# upperArm.net
KiCad netlist of a schematic drawn in EAGLE
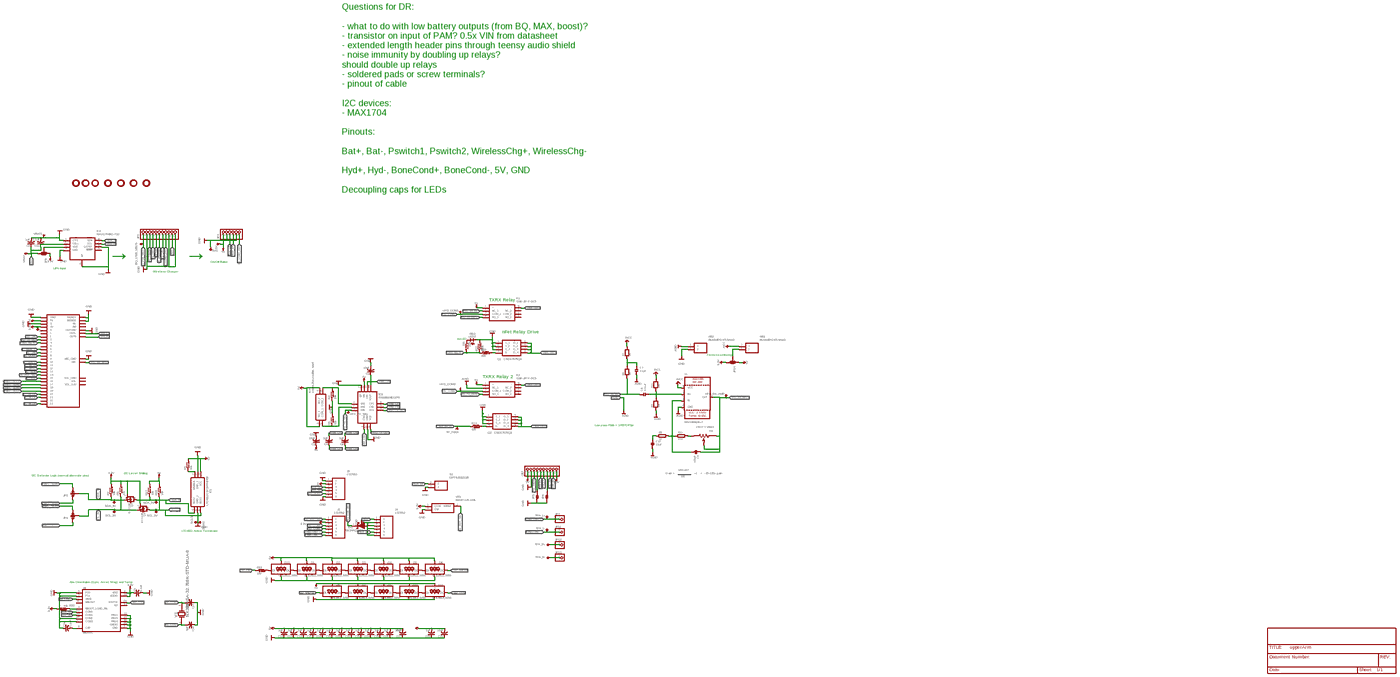
[diagram p0: schematic, sheet 1, overview]
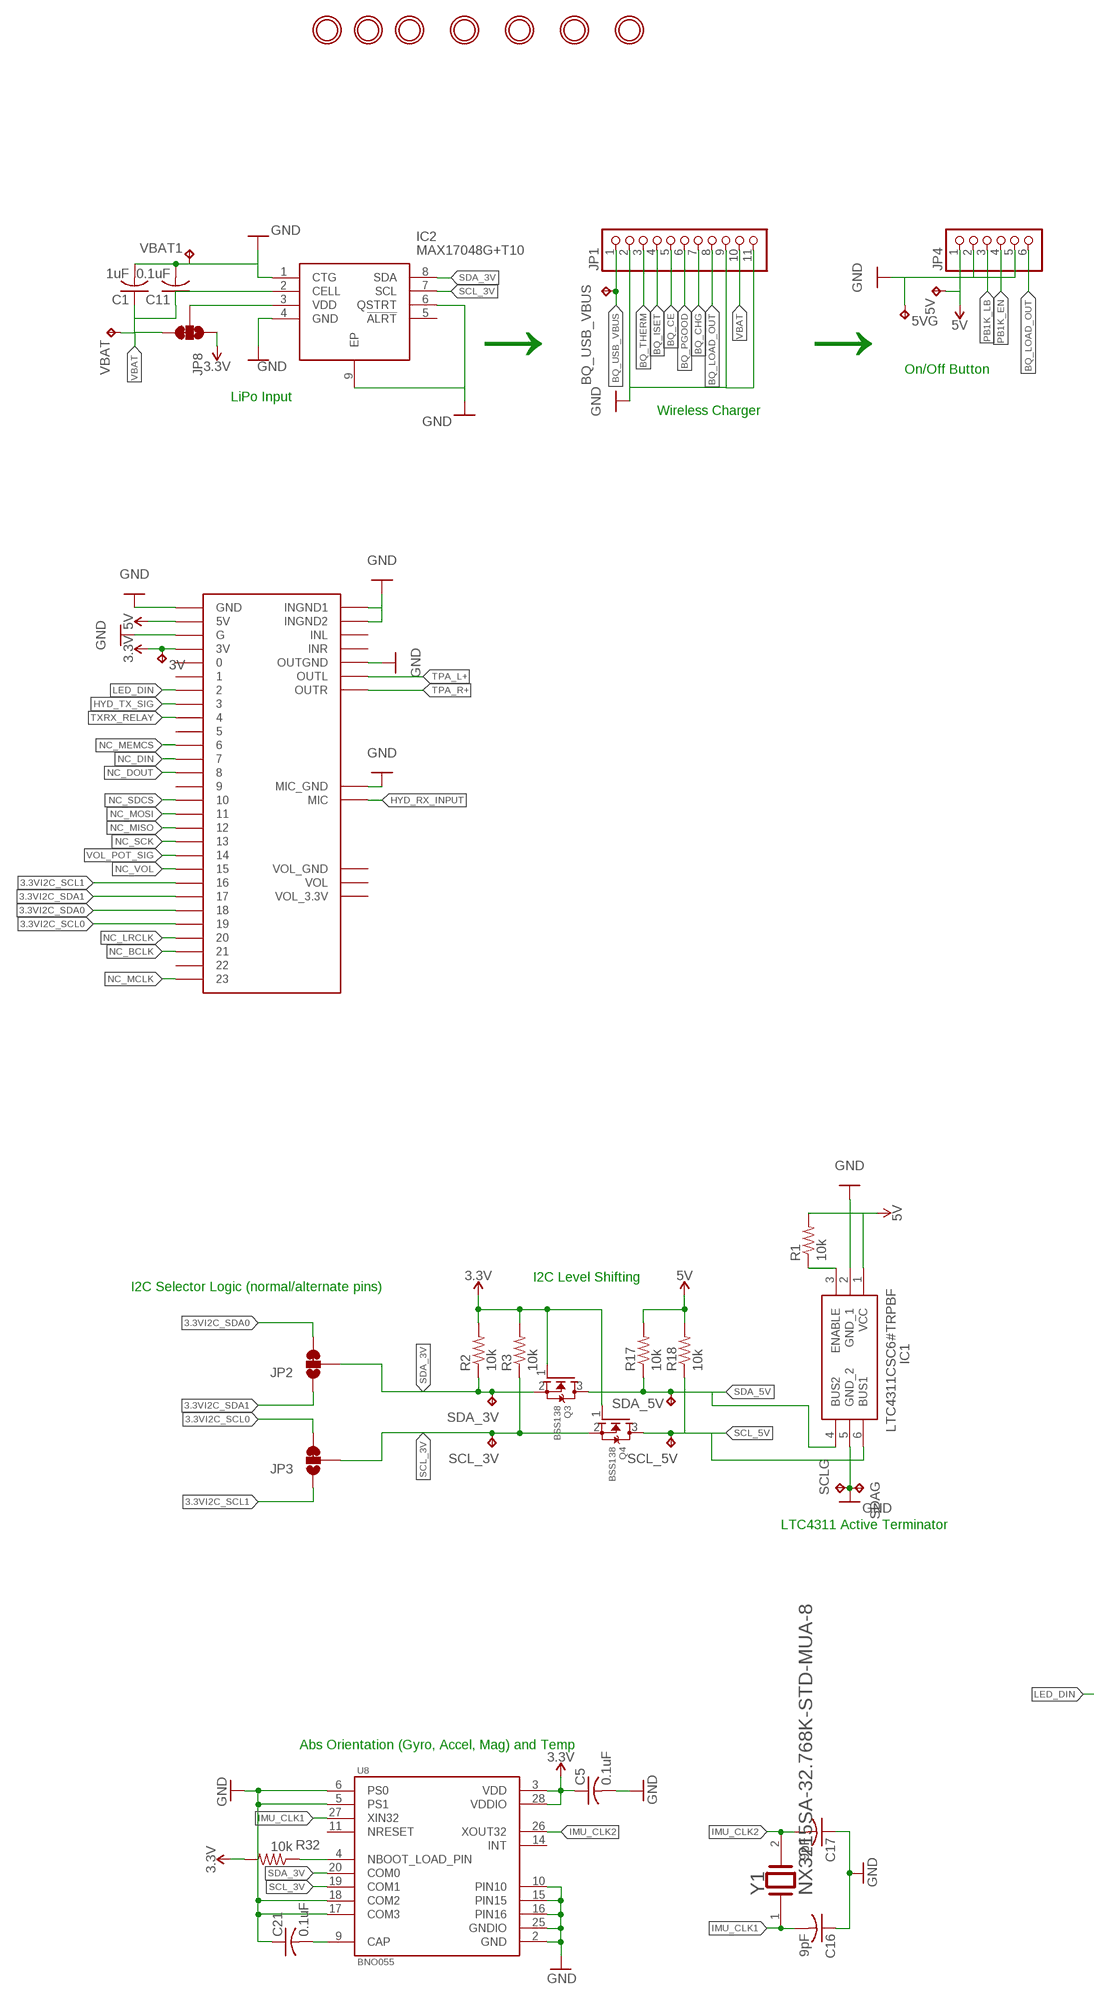
[diagram p1: schematic, sheet 1, part 1 of 4]
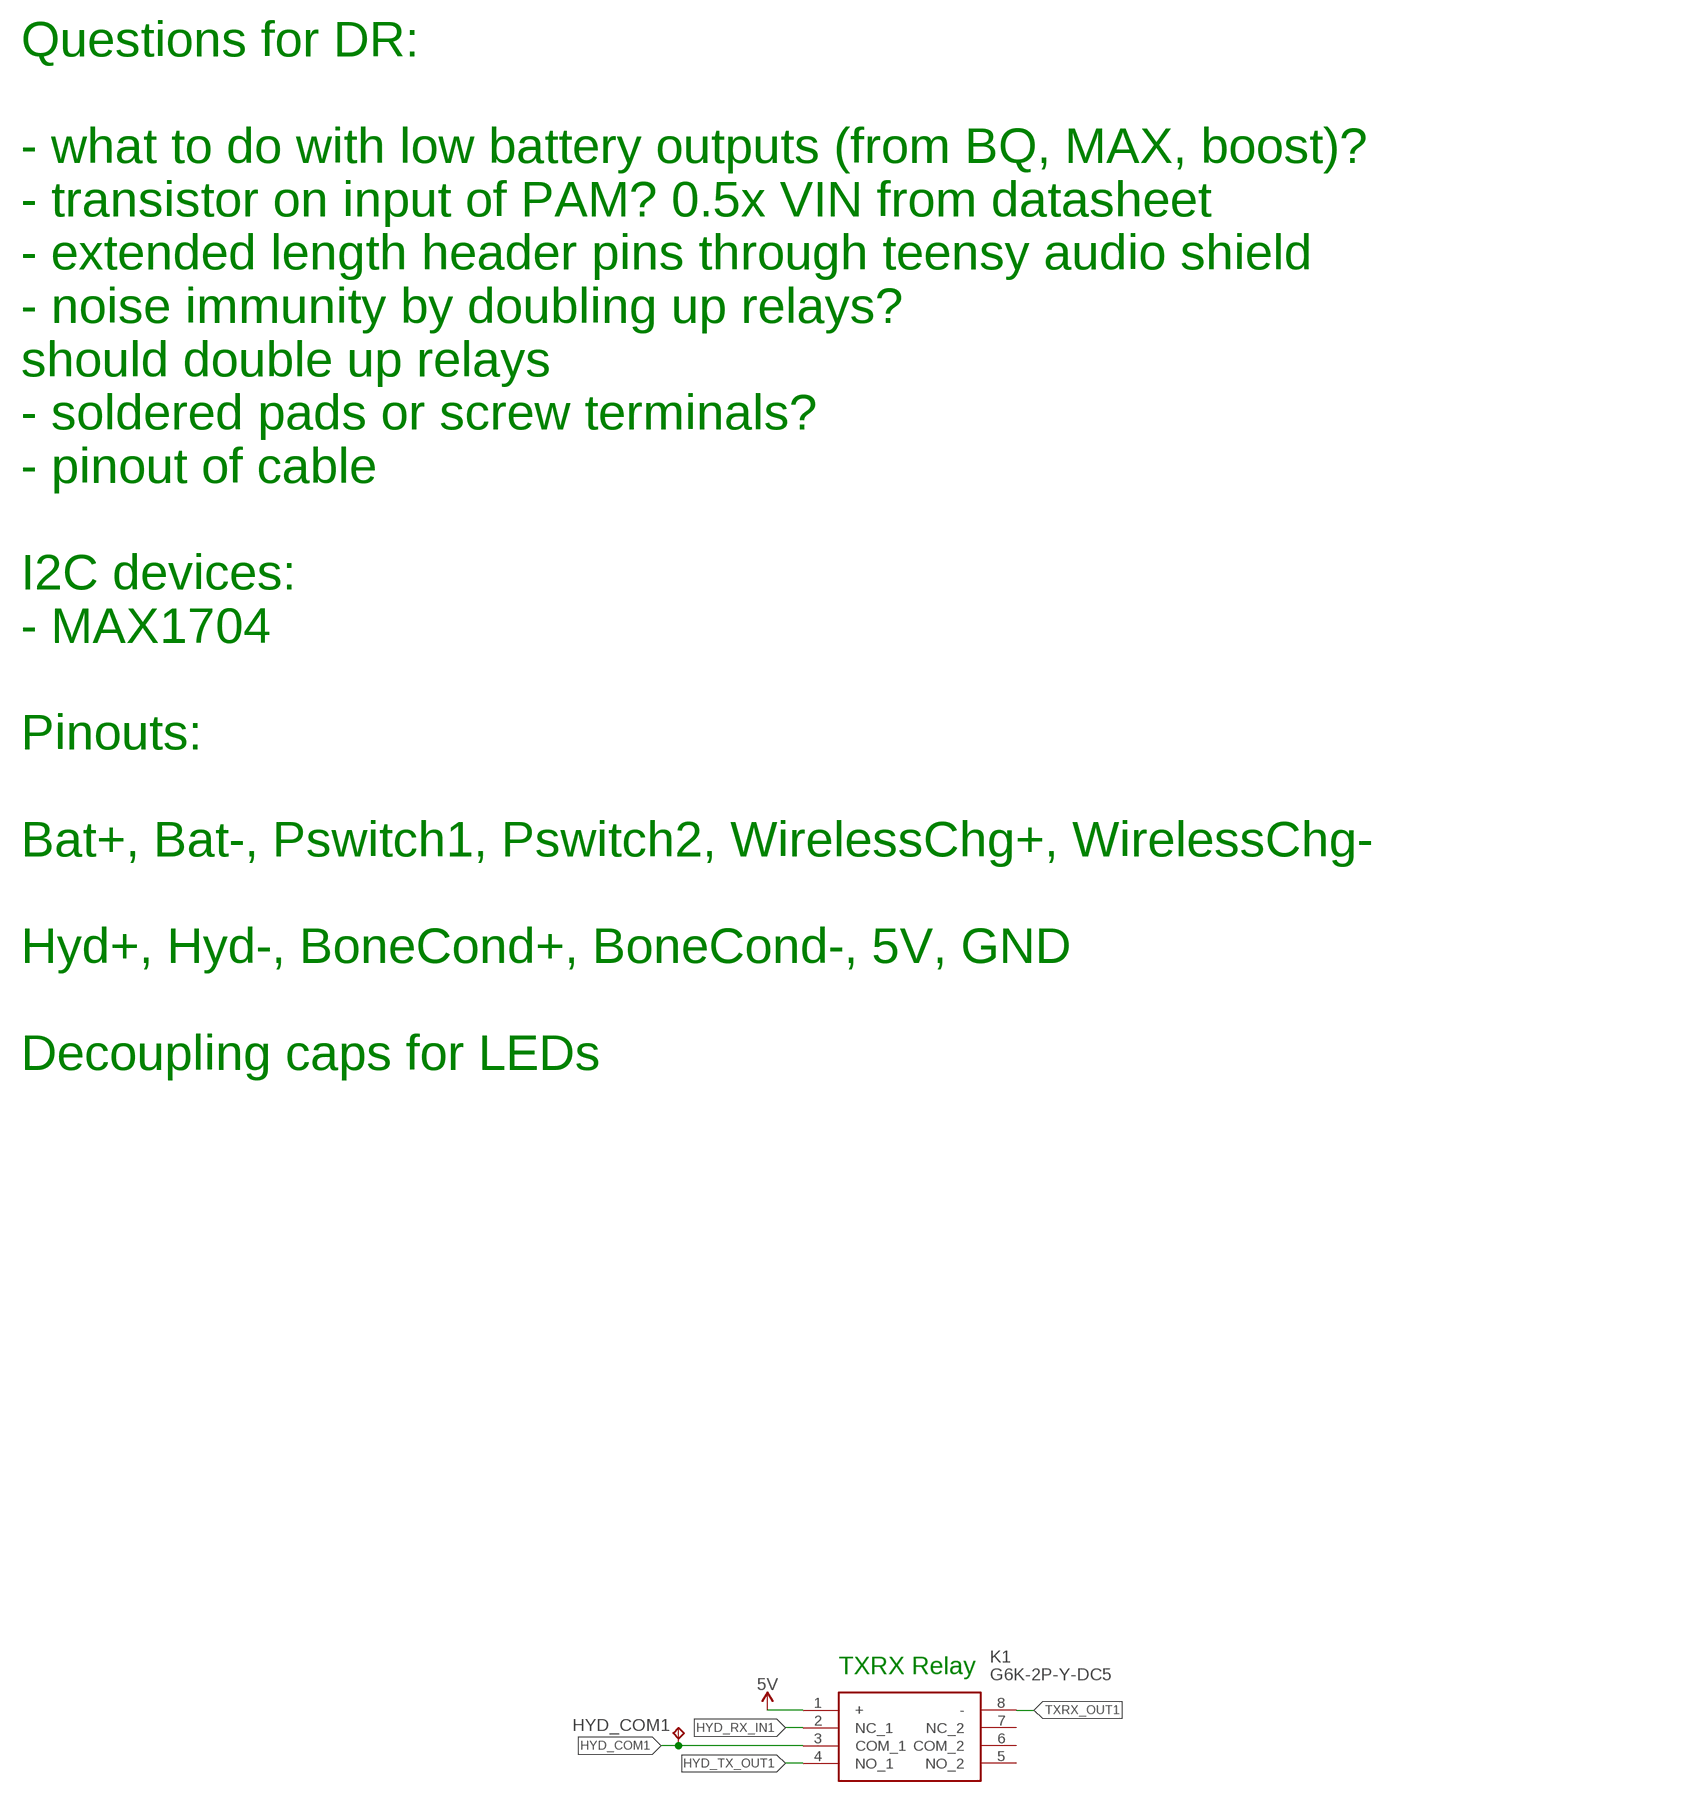
[diagram p2: schematic, sheet 1, part 2 of 4]
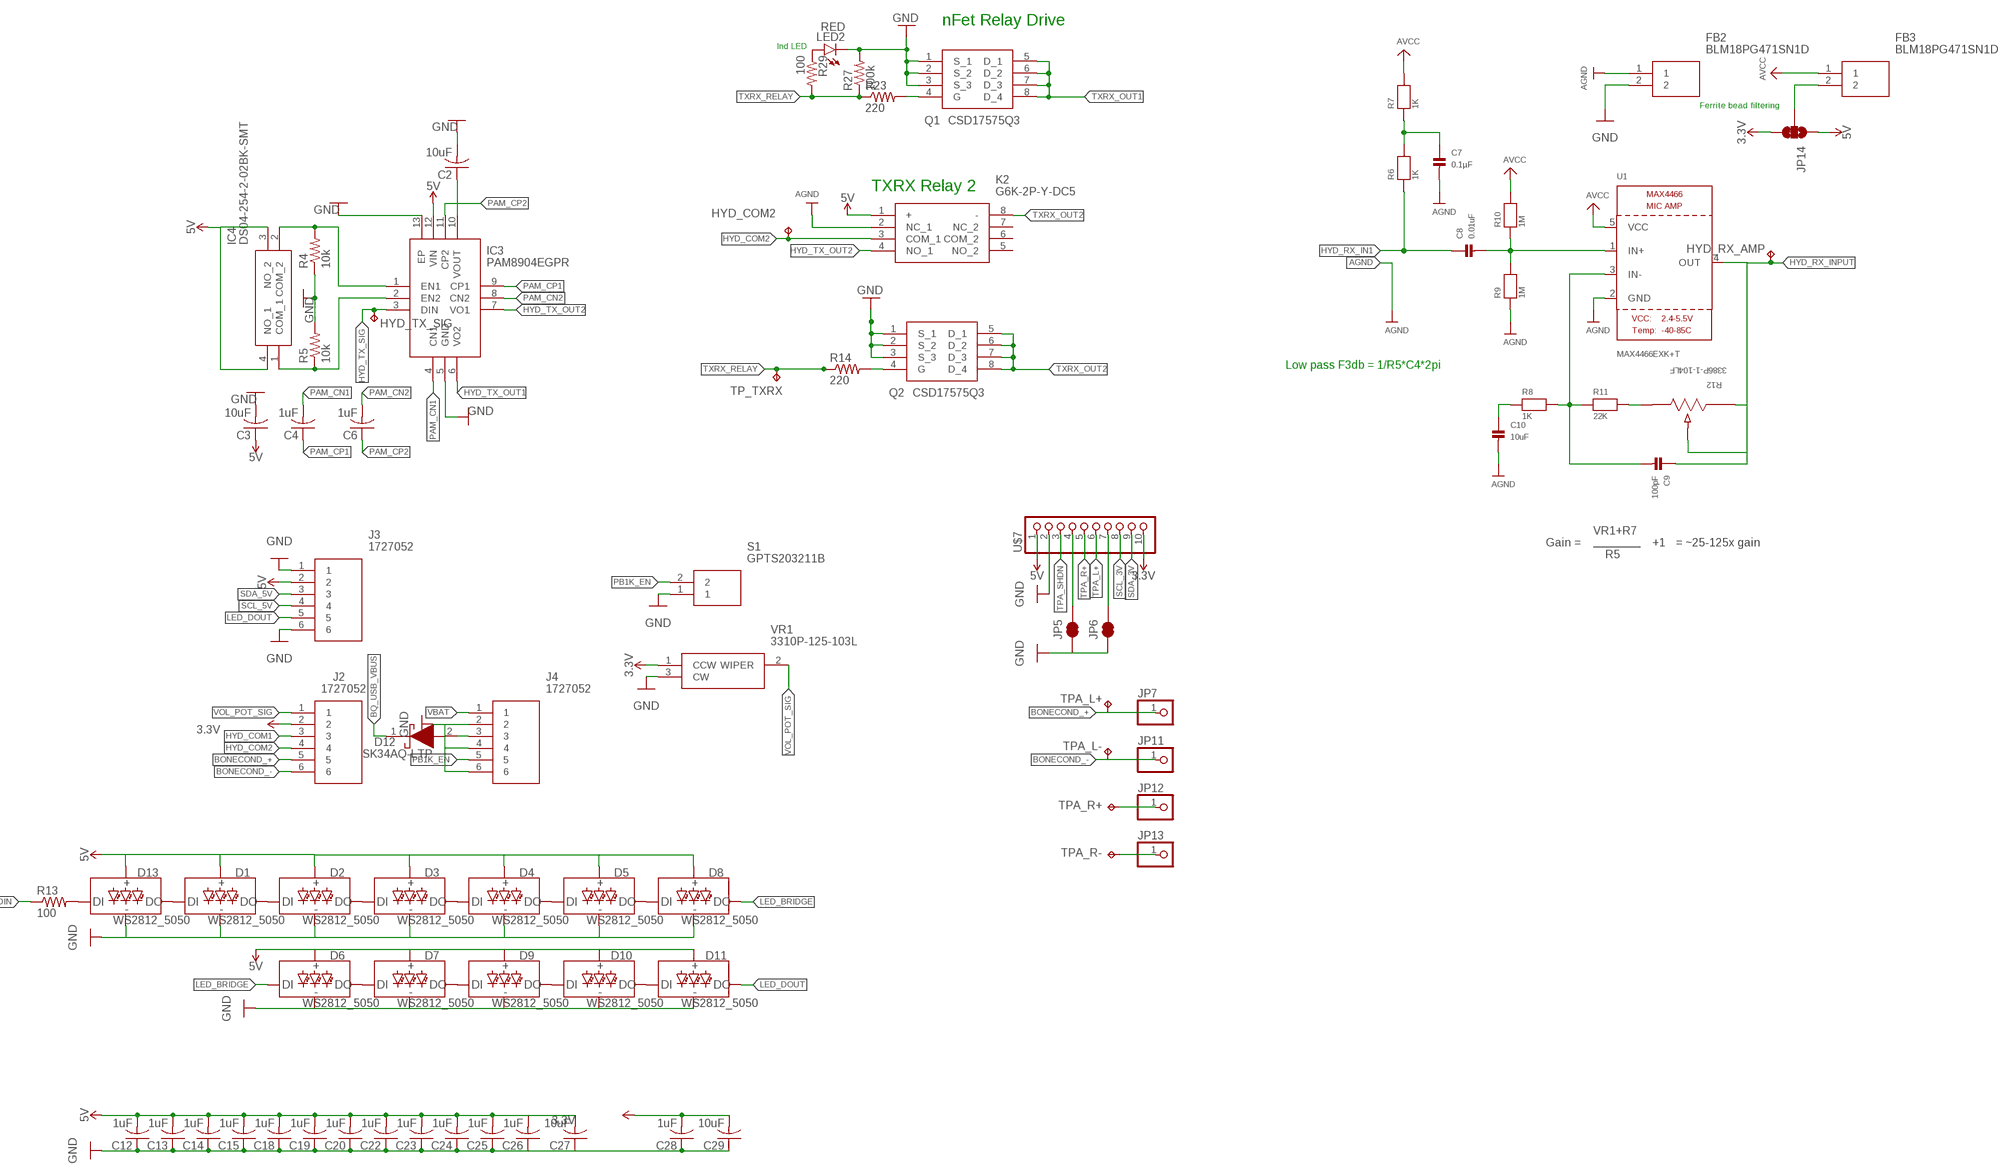
[diagram p3: schematic, sheet 1, part 3 of 4]
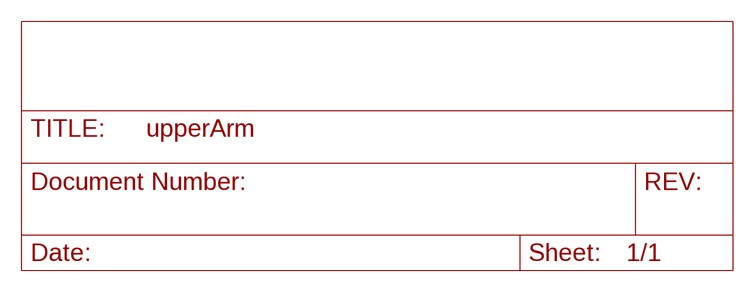
[diagram p4: schematic, sheet 1, part 4 of 4]

(export (version "E")
  (design (tool "Eeschema 10.0.6"))
  (components
    (comp (ref "3V")
      (value "TPB1,27")
      (footprint "eagle-import:B1,27")
      (libsource (lib "eagle-import") (part "TPB1,27"))
    )
    (comp (ref "5V")
      (value "TPB1,27")
      (footprint "eagle-import:B1,27")
      (libsource (lib "eagle-import") (part "TPB1,27"))
    )
    (comp (ref "5VG")
      (value "TPB1,27")
      (footprint "eagle-import:B1,27")
      (libsource (lib "eagle-import") (part "TPB1,27"))
    )
    (comp (ref "BQ_USB_VBUS")
      (value "TPB1,27")
      (footprint "eagle-import:B1,27")
      (libsource (lib "eagle-import") (part "TPB1,27"))
    )
    (comp (ref "C1")
      (value "1uF")
      (footprint "eagle-import:C0805")
      (libsource (lib "eagle-import") (part "C-USC0805"))
    )
    (comp (ref "C2")
      (value "10uF")
      (footprint "eagle-import:C0805")
      (libsource (lib "eagle-import") (part "C-USC0805"))
    )
    (comp (ref "C3")
      (value "10uF")
      (footprint "eagle-import:C0805")
      (libsource (lib "eagle-import") (part "C-USC0805"))
    )
    (comp (ref "C4")
      (value "1uF")
      (footprint "eagle-import:C0805")
      (libsource (lib "eagle-import") (part "C-USC0805"))
    )
    (comp (ref "C5")
      (value "0.1uF")
      (footprint "eagle-import:C0805")
      (libsource (lib "eagle-import") (part "C-USC0805"))
    )
    (comp (ref "C6")
      (value "1uF")
      (footprint "eagle-import:C0805")
      (libsource (lib "eagle-import") (part "C-USC0805"))
    )
    (comp (ref "C7")
      (value "0.1µF")
      (footprint "eagle-import:0805")
      (libsource (lib "eagle-import") (part "CAP_CERAMIC0805"))
    )
    (comp (ref "C8")
      (value "0.01uF")
      (footprint "eagle-import:0805")
      (libsource (lib "eagle-import") (part "CAP_CERAMIC0805"))
    )
    (comp (ref "C9")
      (value "100pF")
      (footprint "eagle-import:0805")
      (libsource (lib "eagle-import") (part "CAP_CERAMIC0805"))
    )
    (comp (ref "C10")
      (value "10uF")
      (footprint "eagle-import:0805")
      (libsource (lib "eagle-import") (part "CAP_CERAMIC0805"))
    )
    (comp (ref "C11")
      (value "0.1uF")
      (footprint "eagle-import:C0805")
      (libsource (lib "eagle-import") (part "C-USC0805"))
    )
    (comp (ref "C12")
      (value "1uF")
      (footprint "eagle-import:C0805")
      (libsource (lib "eagle-import") (part "C-USC0805"))
    )
    (comp (ref "C13")
      (value "1uF")
      (footprint "eagle-import:C0805")
      (libsource (lib "eagle-import") (part "C-USC0805"))
    )
    (comp (ref "C14")
      (value "1uF")
      (footprint "eagle-import:C0805")
      (libsource (lib "eagle-import") (part "C-USC0805"))
    )
    (comp (ref "C15")
      (value "1uF")
      (footprint "eagle-import:C0805")
      (libsource (lib "eagle-import") (part "C-USC0805"))
    )
    (comp (ref "C16")
      (value "9pF")
      (footprint "eagle-import:C0805")
      (libsource (lib "eagle-import") (part "C-USC0805"))
    )
    (comp (ref "C17")
      (value "9pF")
      (footprint "eagle-import:C0805")
      (libsource (lib "eagle-import") (part "C-USC0805"))
    )
    (comp (ref "C18")
      (value "1uF")
      (footprint "eagle-import:C0805")
      (libsource (lib "eagle-import") (part "C-USC0805"))
    )
    (comp (ref "C19")
      (value "1uF")
      (footprint "eagle-import:C0805")
      (libsource (lib "eagle-import") (part "C-USC0805"))
    )
    (comp (ref "C20")
      (value "1uF")
      (footprint "eagle-import:C0805")
      (libsource (lib "eagle-import") (part "C-USC0805"))
    )
    (comp (ref "C21")
      (value "0.1uF")
      (footprint "eagle-import:C0805")
      (libsource (lib "eagle-import") (part "C-USC0805"))
    )
    (comp (ref "C22")
      (value "1uF")
      (footprint "eagle-import:C0805")
      (libsource (lib "eagle-import") (part "C-USC0805"))
    )
    (comp (ref "C23")
      (value "1uF")
      (footprint "eagle-import:C0805")
      (libsource (lib "eagle-import") (part "C-USC0805"))
    )
    (comp (ref "C24")
      (value "1uF")
      (footprint "eagle-import:C0805")
      (libsource (lib "eagle-import") (part "C-USC0805"))
    )
    (comp (ref "C25")
      (value "1uF")
      (footprint "eagle-import:C0805")
      (libsource (lib "eagle-import") (part "C-USC0805"))
    )
    (comp (ref "C26")
      (value "1uF")
      (footprint "eagle-import:C0805")
      (libsource (lib "eagle-import") (part "C-USC0805"))
    )
    (comp (ref "C27")
      (value "10uF")
      (footprint "eagle-import:C0805")
      (libsource (lib "eagle-import") (part "C-USC0805"))
    )
    (comp (ref "C28")
      (value "1uF")
      (footprint "eagle-import:C0805")
      (libsource (lib "eagle-import") (part "C-USC0805"))
    )
    (comp (ref "C29")
      (value "10uF")
      (footprint "eagle-import:C0805")
      (libsource (lib "eagle-import") (part "C-USC0805"))
    )
    (comp (ref "D1")
      (value "WS2812_5050")
      (footprint "eagle-import:WS2812-5X5-4PIN")
      (libsource (lib "eagle-import") (part "WS2812_5050"))
    )
    (comp (ref "D2")
      (value "WS2812_5050")
      (footprint "eagle-import:WS2812-5X5-4PIN")
      (libsource (lib "eagle-import") (part "WS2812_5050"))
    )
    (comp (ref "D3")
      (value "WS2812_5050")
      (footprint "eagle-import:WS2812-5X5-4PIN")
      (libsource (lib "eagle-import") (part "WS2812_5050"))
    )
    (comp (ref "D4")
      (value "WS2812_5050")
      (footprint "eagle-import:WS2812-5X5-4PIN")
      (libsource (lib "eagle-import") (part "WS2812_5050"))
    )
    (comp (ref "D5")
      (value "WS2812_5050")
      (footprint "eagle-import:WS2812-5X5-4PIN")
      (libsource (lib "eagle-import") (part "WS2812_5050"))
    )
    (comp (ref "D6")
      (value "WS2812_5050")
      (footprint "eagle-import:WS2812-5X5-4PIN")
      (libsource (lib "eagle-import") (part "WS2812_5050"))
    )
    (comp (ref "D7")
      (value "WS2812_5050")
      (footprint "eagle-import:WS2812-5X5-4PIN")
      (libsource (lib "eagle-import") (part "WS2812_5050"))
    )
    (comp (ref "D8")
      (value "WS2812_5050")
      (footprint "eagle-import:WS2812-5X5-4PIN")
      (libsource (lib "eagle-import") (part "WS2812_5050"))
    )
    (comp (ref "D9")
      (value "WS2812_5050")
      (footprint "eagle-import:WS2812-5X5-4PIN")
      (libsource (lib "eagle-import") (part "WS2812_5050"))
    )
    (comp (ref "D10")
      (value "WS2812_5050")
      (footprint "eagle-import:WS2812-5X5-4PIN")
      (libsource (lib "eagle-import") (part "WS2812_5050"))
    )
    (comp (ref "D11")
      (value "WS2812_5050")
      (footprint "eagle-import:WS2812-5X5-4PIN")
      (libsource (lib "eagle-import") (part "WS2812_5050"))
    )
    (comp (ref "D12")
      (value "SK34AQ-LTP")
      (footprint "eagle-import:DIOM5226X244N")
      (fields (field (name "MOUSER_PART_NUMBER") "833-SK34AQ-LTP"))
      (libsource (lib "eagle-import") (part "SK34AQ-LTP"))
    )
    (comp (ref "D13")
      (value "WS2812_5050")
      (footprint "eagle-import:WS2812-5X5-4PIN")
      (libsource (lib "eagle-import") (part "WS2812_5050"))
    )
    (comp (ref "FB2")
      (value "BLM18PG471SN1D")
      (footprint "eagle-import:BLM18SP221SN1B")
      (fields (field (name "MOUSER_PART_NUMBER") "81-BLM18PG471SN1D"))
      (libsource (lib "eagle-import") (part "BLM18PG471SN1D"))
    )
    (comp (ref "FB3")
      (value "BLM18PG471SN1D")
      (footprint "eagle-import:BLM18SP221SN1B")
      (fields (field (name "MOUSER_PART_NUMBER") "81-BLM18PG471SN1D"))
      (libsource (lib "eagle-import") (part "BLM18PG471SN1D"))
    )
    (comp (ref "HYD_COM1")
      (value "TPB1,27")
      (footprint "eagle-import:B1,27")
      (libsource (lib "eagle-import") (part "TPB1,27"))
    )
    (comp (ref "HYD_COM2")
      (value "TPB1,27")
      (footprint "eagle-import:B1,27")
      (libsource (lib "eagle-import") (part "TPB1,27"))
    )
    (comp (ref "HYD_RX_AMP")
      (value "TPB1,27")
      (footprint "eagle-import:B1,27")
      (libsource (lib "eagle-import") (part "TPB1,27"))
    )
    (comp (ref "HYD_TX_SIG")
      (value "TPB1,27")
      (footprint "eagle-import:B1,27")
      (libsource (lib "eagle-import") (part "TPB1,27"))
    )
    (comp (ref "IC1")
      (value "LTC4311CSC6#TRPBF")
      (footprint "eagle-import:SOT65P210X100-6N")
      (fields (field (name "MOUSER_PART_NUMBER") "584-LTC4311CSC6TRPBF"))
      (libsource (lib "eagle-import") (part "LTC4311CSC6#TRPBF"))
    )
    (comp (ref "IC2")
      (value "MAX17048G+T10")
      (footprint "eagle-import:SON50P200X200X80-9N")
      (fields (field (name "MOUSER_PART_NUMBER") "700-MAX17048G+T10"))
      (libsource (lib "eagle-import") (part "MAX17048G+T10"))
    )
    (comp (ref "IC3")
      (value "PAM8904EGPR")
      (footprint "eagle-import:QFN40P200X200X80-13N")
      (fields (field (name "MOUSER_PART_NUMBER") "621-PAM8904EGPR"))
      (libsource (lib "eagle-import") (part "PAM8904EGPR"))
    )
    (comp (ref "IC4")
      (value "DS04-254-2-02BK-SMT")
      (footprint "eagle-import:DS04254202BKSMT")
      (fields (field (name "MOUSER_PART_NUMBER") "490-DS04254202BK-SMT"))
      (libsource (lib "eagle-import") (part "DS04-254-2-02BK-SMT"))
    )
    (comp (ref "J2")
      (value "1727052")
      (footprint "eagle-import:1727052")
      (fields (field (name "MOUSER_PART_NUMBER") "651-1727052"))
      (libsource (lib "eagle-import") (part "1727052"))
    )
    (comp (ref "J3")
      (value "1727052")
      (footprint "eagle-import:1727052")
      (fields (field (name "MOUSER_PART_NUMBER") "651-1727052"))
      (libsource (lib "eagle-import") (part "1727052"))
    )
    (comp (ref "J4")
      (value "1727052")
      (footprint "eagle-import:1727052")
      (fields (field (name "MOUSER_PART_NUMBER") "651-1727052"))
      (libsource (lib "eagle-import") (part "1727052"))
    )
    (comp (ref "JP1")
      (value "PINHD-1X11")
      (footprint "eagle-import:1X11")
      (libsource (lib "eagle-import") (part "PINHD-1X11"))
    )
    (comp (ref "JP2")
      (value "JUMPER-SMT_3_1-NC_TRACE_NO-SILK")
      (footprint "eagle-import:SMT-JUMPER_3_1-NC_TRACE_NO-SILK")
      (libsource (lib "eagle-import") (part "JUMPER-SMT_3_1-NC_TRACE_NO-SILK"))
    )
    (comp (ref "JP3")
      (value "JUMPER-SMT_3_1-NC_TRACE_NO-SILK")
      (footprint "eagle-import:SMT-JUMPER_3_1-NC_TRACE_NO-SILK")
      (libsource (lib "eagle-import") (part "JUMPER-SMT_3_1-NC_TRACE_NO-SILK"))
    )
    (comp (ref "JP4")
      (value "PINHD-1X6")
      (footprint "eagle-import:1X06")
      (libsource (lib "eagle-import") (part "PINHD-1X6"))
    )
    (comp (ref "JP5")
      (value "JUMPER-SMT_2_NC_TRACE_NO-SILK")
      (footprint "eagle-import:SMT-JUMPER_2_NC_TRACE_NO-SILK")
      (libsource (lib "eagle-import") (part "JUMPER-SMT_2_NC_TRACE_NO-SILK"))
    )
    (comp (ref "JP6")
      (value "JUMPER-SMT_2_NC_TRACE_NO-SILK")
      (footprint "eagle-import:SMT-JUMPER_2_NC_TRACE_NO-SILK")
      (libsource (lib "eagle-import") (part "JUMPER-SMT_2_NC_TRACE_NO-SILK"))
    )
    (comp (ref "JP7")
      (value "PINHD-1X1")
      (footprint "eagle-import:1X01")
      (libsource (lib "eagle-import") (part "PINHD-1X1"))
    )
    (comp (ref "JP8")
      (value "JUMPER-SMT_3_1-NC_TRACE_NO-SILK")
      (footprint "eagle-import:SMT-JUMPER_3_1-NC_TRACE_NO-SILK")
      (libsource (lib "eagle-import") (part "JUMPER-SMT_3_1-NC_TRACE_NO-SILK"))
    )
    (comp (ref "JP11")
      (value "PINHD-1X1")
      (footprint "eagle-import:1X01")
      (libsource (lib "eagle-import") (part "PINHD-1X1"))
    )
    (comp (ref "JP12")
      (value "PINHD-1X1")
      (footprint "eagle-import:1X01")
      (libsource (lib "eagle-import") (part "PINHD-1X1"))
    )
    (comp (ref "JP13")
      (value "PINHD-1X1")
      (footprint "eagle-import:1X01")
      (libsource (lib "eagle-import") (part "PINHD-1X1"))
    )
    (comp (ref "JP14")
      (value "JUMPER-SMT_3_1-NC_TRACE_NO-SILK")
      (footprint "eagle-import:SMT-JUMPER_3_1-NC_TRACE_NO-SILK")
      (libsource (lib "eagle-import") (part "JUMPER-SMT_3_1-NC_TRACE_NO-SILK"))
    )
    (comp (ref "K1")
      (value "G6K-2P-Y-DC5")
      (footprint "eagle-import:G6K2PYDC12")
      (fields (field (name "MOUSER_PART_NUMBER") "653-G6K-2P-Y-DC5"))
      (libsource (lib "eagle-import") (part "G6K-2P-Y-DC5"))
    )
    (comp (ref "K2")
      (value "G6K-2P-Y-DC5")
      (footprint "eagle-import:G6K2PYDC12")
      (fields (field (name "MOUSER_PART_NUMBER") "653-G6K-2P-Y-DC5"))
      (libsource (lib "eagle-import") (part "G6K-2P-Y-DC5"))
    )
    (comp (ref "LED2")
      (value "RED")
      (footprint "eagle-import:CHIP-LED0805")
      (libsource (lib "eagle-import") (part "LEDCHIP-LED0805"))
    )
    (comp (ref "Q1")
      (value "CSD17575Q3")
      (footprint "eagle-import:CSD16327")
      (fields (field (name "MOUSER_PART_NUMBER") "595-CSD17575Q3"))
      (libsource (lib "eagle-import") (part "CSD17575Q3"))
    )
    (comp (ref "Q2")
      (value "CSD17575Q3")
      (footprint "eagle-import:CSD16327")
      (fields (field (name "MOUSER_PART_NUMBER") "595-CSD17575Q3"))
      (libsource (lib "eagle-import") (part "CSD17575Q3"))
    )
    (comp (ref "Q3")
      (value "BSS138")
      (footprint "eagle-import:SOT23-WIDE")
      (libsource (lib "eagle-import") (part "MOSFET-NWIDE"))
    )
    (comp (ref "Q4")
      (value "BSS138")
      (footprint "eagle-import:SOT23-WIDE")
      (libsource (lib "eagle-import") (part "MOSFET-NWIDE"))
    )
    (comp (ref "R1")
      (value "10k")
      (footprint "eagle-import:R0805")
      (libsource (lib "eagle-import") (part "R-US_R0805"))
    )
    (comp (ref "R2")
      (value "10k")
      (footprint "eagle-import:R0805")
      (libsource (lib "eagle-import") (part "R-US_R0805"))
    )
    (comp (ref "R3")
      (value "10k")
      (footprint "eagle-import:R0805")
      (libsource (lib "eagle-import") (part "R-US_R0805"))
    )
    (comp (ref "R4")
      (value "10k")
      (footprint "eagle-import:R0805")
      (libsource (lib "eagle-import") (part "R-US_R0805"))
    )
    (comp (ref "R5")
      (value "10k")
      (footprint "eagle-import:R0805")
      (libsource (lib "eagle-import") (part "R-US_R0805"))
    )
    (comp (ref "R6")
      (value "1K")
      (footprint "eagle-import:0805")
      (libsource (lib "eagle-import") (part "RESISTOR0805"))
    )
    (comp (ref "R7")
      (value "1K")
      (footprint "eagle-import:0805")
      (libsource (lib "eagle-import") (part "RESISTOR0805"))
    )
    (comp (ref "R8")
      (value "1K")
      (footprint "eagle-import:0805")
      (libsource (lib "eagle-import") (part "RESISTOR0805"))
    )
    (comp (ref "R9")
      (value "1M")
      (footprint "eagle-import:0805")
      (libsource (lib "eagle-import") (part "RESISTOR0805"))
    )
    (comp (ref "R10")
      (value "1M")
      (footprint "eagle-import:0805")
      (libsource (lib "eagle-import") (part "RESISTOR0805"))
    )
    (comp (ref "R11")
      (value "22K")
      (footprint "eagle-import:0805")
      (libsource (lib "eagle-import") (part "RESISTOR0805"))
    )
    (comp (ref "R12")
      (value "3386P-1-104LF")
      (footprint "eagle-import:POT_3386P")
      (fields (field (name "COPYRIGHT") "Copyright (C) 2024 Ultra Librarian. All rights reserved."))
      (libsource (lib "eagle-import") (part "3386P-1-104LF"))
    )
    (comp (ref "R13")
      (value "100")
      (footprint "eagle-import:R0603")
      (libsource (lib "eagle-import") (part "R-US_R0603"))
    )
    (comp (ref "R14")
      (value "220")
      (footprint "eagle-import:R0805")
      (libsource (lib "eagle-import") (part "R-US_R0805"))
    )
    (comp (ref "R17")
      (value "10k")
      (footprint "eagle-import:R0805")
      (libsource (lib "eagle-import") (part "R-US_R0805"))
    )
    (comp (ref "R18")
      (value "10k")
      (footprint "eagle-import:R0805")
      (libsource (lib "eagle-import") (part "R-US_R0805"))
    )
    (comp (ref "R23")
      (value "220")
      (footprint "eagle-import:R0805")
      (libsource (lib "eagle-import") (part "R-US_R0805"))
    )
    (comp (ref "R27")
      (value "100k")
      (footprint "eagle-import:R0805")
      (libsource (lib "eagle-import") (part "R-US_R0805"))
    )
    (comp (ref "R29")
      (value "100")
      (footprint "eagle-import:R0805")
      (libsource (lib "eagle-import") (part "R-US_R0805"))
    )
    (comp (ref "R32")
      (value "10k")
      (footprint "eagle-import:R0805")
      (libsource (lib "eagle-import") (part "R-US_R0805"))
    )
    (comp (ref "S1")
      (value "GPTS203211B")
      (footprint "eagle-import:GPTS203211B")
      (fields (field (name "MOUSER_PART_NUMBER") "629-GPTS203211B"))
      (libsource (lib "eagle-import") (part "GPTS203211B"))
    )
    (comp (ref "SCLG")
      (value "TPB1,27")
      (footprint "eagle-import:B1,27")
      (libsource (lib "eagle-import") (part "TPB1,27"))
    )
    (comp (ref "SCL_3V")
      (value "TPB1,27")
      (footprint "eagle-import:B1,27")
      (libsource (lib "eagle-import") (part "TPB1,27"))
    )
    (comp (ref "SCL_5V")
      (value "TPB1,27")
      (footprint "eagle-import:B1,27")
      (libsource (lib "eagle-import") (part "TPB1,27"))
    )
    (comp (ref "SDAG")
      (value "TPB1,27")
      (footprint "eagle-import:B1,27")
      (libsource (lib "eagle-import") (part "TPB1,27"))
    )
    (comp (ref "SDA_3V")
      (value "TPB1,27")
      (footprint "eagle-import:B1,27")
      (libsource (lib "eagle-import") (part "TPB1,27"))
    )
    (comp (ref "SDA_5V")
      (value "TPB1,27")
      (footprint "eagle-import:B1,27")
      (libsource (lib "eagle-import") (part "TPB1,27"))
    )
    (comp (ref "TPA_L+")
      (value "TPB1,27")
      (footprint "eagle-import:B1,27")
      (libsource (lib "eagle-import") (part "TPB1,27"))
    )
    (comp (ref "TPA_L-")
      (value "TPB1,27")
      (footprint "eagle-import:B1,27")
      (libsource (lib "eagle-import") (part "TPB1,27"))
    )
    (comp (ref "TPA_R+")
      (value "TPB1,27")
      (footprint "eagle-import:B1,27")
      (libsource (lib "eagle-import") (part "TPB1,27"))
    )
    (comp (ref "TPA_R-")
      (value "TPB1,27")
      (footprint "eagle-import:B1,27")
      (libsource (lib "eagle-import") (part "TPB1,27"))
    )
    (comp (ref "TP_TXRX")
      (value "TPB1,27")
      (footprint "eagle-import:B1,27")
      (libsource (lib "eagle-import") (part "TPB1,27"))
    )
    (comp (ref "U$1")
      (value "AUDIOSHIELD")
      (footprint "eagle-import:AUDIOSHIELD")
      (libsource (lib "eagle-import") (part "AUDIOSHIELD"))
    )
    (comp (ref "U$7")
      (value "PINHD-1X10")
      (footprint "eagle-import:1X10")
      (libsource (lib "eagle-import") (part "PINHD-1X10"))
    )
    (comp (ref "U$11")
      (value "MOUNTINGHOLE2.5")
      (footprint "eagle-import:MOUNTINGHOLE_2.5_PLATED")
      (libsource (lib "eagle-import") (part "MOUNTINGHOLE2.5"))
    )
    (comp (ref "U$14")
      (value "MOUNTINGHOLE2.5")
      (footprint "eagle-import:MOUNTINGHOLE_2.5_PLATED")
      (libsource (lib "eagle-import") (part "MOUNTINGHOLE2.5"))
    )
    (comp (ref "U$15")
      (value "MOUNTINGHOLE2.5")
      (footprint "eagle-import:MOUNTINGHOLE_2.5_PLATED")
      (libsource (lib "eagle-import") (part "MOUNTINGHOLE2.5"))
    )
    (comp (ref "U$16")
      (value "MOUNTINGHOLE2.5")
      (footprint "eagle-import:MOUNTINGHOLE_2.5_PLATED")
      (libsource (lib "eagle-import") (part "MOUNTINGHOLE2.5"))
    )
    (comp (ref "U$17")
      (value "MOUNTINGHOLE2.5")
      (footprint "eagle-import:MOUNTINGHOLE_2.5_PLATED")
      (libsource (lib "eagle-import") (part "MOUNTINGHOLE2.5"))
    )
    (comp (ref "U$18")
      (value "MOUNTINGHOLE2.5")
      (footprint "eagle-import:MOUNTINGHOLE_2.5_PLATED")
      (libsource (lib "eagle-import") (part "MOUNTINGHOLE2.5"))
    )
    (comp (ref "U$19")
      (value "MOUNTINGHOLE2.5")
      (footprint "eagle-import:MOUNTINGHOLE_2.5_PLATED")
      (libsource (lib "eagle-import") (part "MOUNTINGHOLE2.5"))
    )
    (comp (ref "U1")
      (value "MAX4466EXK+T")
      (footprint "eagle-import:SC70-5")
      (libsource (lib "eagle-import") (part "MAX4466{dblquote}{dblquote}"))
    )
    (comp (ref "U8")
      (value "BNO055")
      (footprint "eagle-import:LGA28R50P4X10_380X520X100")
      (fields (field (name "MF") "Bosch"))
      (libsource (lib "eagle-import") (part "BNO055"))
    )
    (comp (ref "VBAT")
      (value "TPB1,27")
      (footprint "eagle-import:B1,27")
      (libsource (lib "eagle-import") (part "TPB1,27"))
    )
    (comp (ref "VBAT1")
      (value "TPB1,27")
      (footprint "eagle-import:B1,27")
      (libsource (lib "eagle-import") (part "TPB1,27"))
    )
    (comp (ref "VR1")
      (value "3310P-125-103L")
      (footprint "eagle-import:3310P125103L")
      (fields (field (name "MOUSER_PART_NUMBER") "652-3310P-125-103L"))
      (libsource (lib "eagle-import") (part "3310P-125-103L"))
    )
    (comp (ref "Y1")
      (value "NDK_NX3215SA-32.768K-STD-MUA-9")
      (footprint "eagle-import:NDK_NX3215SA-32.768K-STD-MUA-8_0")
      (fields
        (field (name "DIGIKEY_PART_NUMBER") "644-1156-1-ND")
        (field (name "MF") "NDK")
        (field (name "MPN") "NX3215SA-32.768K-STD-MUA-8")
      )
      (libsource (lib "eagle-import") (part "NDK_NX3215SA-32.768K-STD-MUA-8NDK_NX3215SA-32.768K-STD-MUA-8_0_0"))
    )
  )
  (nets
    (net (code "1") (name "3.3V") (class "Default")
      (node (ref "3V") (pin "TP") (pinfunction "TP_TP") (pintype "input"))
      (node (ref "C28") (pin "2") (pinfunction "2_2") (pintype "passive"))
      (node (ref "C29") (pin "2") (pinfunction "2_2") (pintype "passive"))
      (node (ref "C5") (pin "1") (pinfunction "1_1") (pintype "passive"))
      (node (ref "J2") (pin "2") (pinfunction "2_2") (pintype "bidirectional"))
      (node (ref "JP14") (pin "3") (pinfunction "3_3") (pintype "passive"))
      (node (ref "JP8") (pin "1") (pinfunction "1_1") (pintype "passive"))
      (node (ref "Q3") (pin "1") (pinfunction "G_1") (pintype "bidirectional"))
      (node (ref "Q4") (pin "1") (pinfunction "G_1") (pintype "bidirectional"))
      (node (ref "R2") (pin "2") (pinfunction "2_2") (pintype "passive"))
      (node (ref "R3") (pin "2") (pinfunction "2_2") (pintype "passive"))
      (node (ref "R32") (pin "2") (pinfunction "2_2") (pintype "passive"))
      (node (ref "U$1") (pin "3V") (pinfunction "3V_3V") (pintype "bidirectional"))
      (node (ref "U$7") (pin "10") (pinfunction "10_10") (pintype "passive"))
      (node (ref "U8") (pin "28") (pinfunction "VDDIO_28") (pintype "power_in"))
      (node (ref "U8") (pin "3") (pinfunction "VDD_3") (pintype "power_in"))
      (node (ref "VR1") (pin "1") (pinfunction "CCW_1") (pintype "bidirectional"))
    )
    (net (code "2") (name "3.3VI2C_SCL0") (class "Default")
      (node (ref "JP3") (pin "3") (pinfunction "3_3") (pintype "passive"))
      (node (ref "U$1") (pin "19") (pinfunction "19_19") (pintype "bidirectional"))
    )
    (net (code "3") (name "3.3VI2C_SCL1") (class "Default")
      (node (ref "JP3") (pin "1") (pinfunction "1_1") (pintype "passive"))
      (node (ref "U$1") (pin "16") (pinfunction "16_16") (pintype "bidirectional"))
    )
    (net (code "4") (name "3.3VI2C_SDA0") (class "Default")
      (node (ref "JP2") (pin "3") (pinfunction "3_3") (pintype "passive"))
      (node (ref "U$1") (pin "18") (pinfunction "18_18") (pintype "bidirectional"))
    )
    (net (code "5") (name "3.3VI2C_SDA1") (class "Default")
      (node (ref "JP2") (pin "1") (pinfunction "1_1") (pintype "passive"))
      (node (ref "U$1") (pin "17") (pinfunction "17_17") (pintype "bidirectional"))
    )
    (net (code "6") (name "5V") (class "Default")
      (node (ref "5V") (pin "TP") (pinfunction "TP_TP") (pintype "input"))
      (node (ref "C12") (pin "2") (pinfunction "2_2") (pintype "passive"))
      (node (ref "C13") (pin "2") (pinfunction "2_2") (pintype "passive"))
      (node (ref "C14") (pin "2") (pinfunction "2_2") (pintype "passive"))
      (node (ref "C15") (pin "2") (pinfunction "2_2") (pintype "passive"))
      (node (ref "C18") (pin "2") (pinfunction "2_2") (pintype "passive"))
      (node (ref "C19") (pin "2") (pinfunction "2_2") (pintype "passive"))
      (node (ref "C20") (pin "2") (pinfunction "2_2") (pintype "passive"))
      (node (ref "C22") (pin "2") (pinfunction "2_2") (pintype "passive"))
      (node (ref "C23") (pin "2") (pinfunction "2_2") (pintype "passive"))
      (node (ref "C24") (pin "2") (pinfunction "2_2") (pintype "passive"))
      (node (ref "C25") (pin "2") (pinfunction "2_2") (pintype "passive"))
      (node (ref "C26") (pin "2") (pinfunction "2_2") (pintype "passive"))
      (node (ref "C27") (pin "2") (pinfunction "2_2") (pintype "passive"))
      (node (ref "C3") (pin "1") (pinfunction "1_1") (pintype "passive"))
      (node (ref "D1") (pin "VCC") (pinfunction "VCC_VCC") (pintype "bidirectional"))
      (node (ref "D10") (pin "VCC") (pinfunction "VCC_VCC") (pintype "bidirectional"))
      (node (ref "D11") (pin "VCC") (pinfunction "VCC_VCC") (pintype "bidirectional"))
      (node (ref "D13") (pin "VCC") (pinfunction "VCC_VCC") (pintype "bidirectional"))
      (node (ref "D2") (pin "VCC") (pinfunction "VCC_VCC") (pintype "bidirectional"))
      (node (ref "D3") (pin "VCC") (pinfunction "VCC_VCC") (pintype "bidirectional"))
      (node (ref "D4") (pin "VCC") (pinfunction "VCC_VCC") (pintype "bidirectional"))
      (node (ref "D5") (pin "VCC") (pinfunction "VCC_VCC") (pintype "bidirectional"))
      (node (ref "D6") (pin "VCC") (pinfunction "VCC_VCC") (pintype "bidirectional"))
      (node (ref "D7") (pin "VCC") (pinfunction "VCC_VCC") (pintype "bidirectional"))
      (node (ref "D8") (pin "VCC") (pinfunction "VCC_VCC") (pintype "bidirectional"))
      (node (ref "D9") (pin "VCC") (pinfunction "VCC_VCC") (pintype "bidirectional"))
      (node (ref "IC1") (pin "1") (pinfunction "VCC_1") (pintype "bidirectional"))
      (node (ref "IC3") (pin "12") (pinfunction "VIN_12") (pintype "bidirectional"))
      (node (ref "IC4") (pin "3") (pinfunction "NO_2_3") (pintype "bidirectional"))
      (node (ref "IC4") (pin "4") (pinfunction "NO_1_4") (pintype "bidirectional"))
      (node (ref "J3") (pin "2") (pinfunction "2_2") (pintype "bidirectional"))
      (node (ref "JP14") (pin "1") (pinfunction "1_1") (pintype "passive"))
      (node (ref "JP4") (pin "1") (pinfunction "1_1") (pintype "passive"))
      (node (ref "K1") (pin "1") (pinfunction "+_1") (pintype "bidirectional"))
      (node (ref "K2") (pin "1") (pinfunction "+_1") (pintype "bidirectional"))
      (node (ref "R1") (pin "2") (pinfunction "2_2") (pintype "passive"))
      (node (ref "R17") (pin "2") (pinfunction "2_2") (pintype "passive"))
      (node (ref "R18") (pin "2") (pinfunction "2_2") (pintype "passive"))
      (node (ref "U$1") (pin "5V") (pinfunction "5V_5V") (pintype "bidirectional"))
      (node (ref "U$7") (pin "1") (pinfunction "1_1") (pintype "passive"))
    )
    (net (code "7") (name "AGND") (class "Default")
      (node (ref "C10") (pin "2") (pinfunction "P$2_2") (pintype "passive"))
      (node (ref "C7") (pin "2") (pinfunction "P$2_2") (pintype "passive"))
      (node (ref "FB2") (pin "1") (pinfunction "1_1") (pintype "bidirectional"))
      (node (ref "K2") (pin "2") (pinfunction "NC_1_2") (pintype "bidirectional"))
      (node (ref "R9") (pin "1") (pinfunction "1_1") (pintype "passive"))
      (node (ref "U1") (pin "2") (pinfunction "GND_2") (pintype "bidirectional"))
    )
    (net (code "8") (name "AVCC") (class "Default")
      (node (ref "FB3") (pin "1") (pinfunction "1_1") (pintype "bidirectional"))
      (node (ref "R10") (pin "2") (pinfunction "2_2") (pintype "passive"))
      (node (ref "R7") (pin "2") (pinfunction "2_2") (pintype "passive"))
      (node (ref "U1") (pin "5") (pinfunction "VCC_5") (pintype "bidirectional"))
    )
    (net (code "9") (name "BONECOND_+") (class "Default")
      (node (ref "J2") (pin "5") (pinfunction "5_5") (pintype "bidirectional"))
      (node (ref "JP7") (pin "1") (pinfunction "1_1") (pintype "passive"))
      (node (ref "TPA_L+") (pin "TP") (pinfunction "TP_TP") (pintype "input"))
    )
    (net (code "10") (name "BONECOND_-") (class "Default")
      (node (ref "J2") (pin "6") (pinfunction "6_6") (pintype "bidirectional"))
      (node (ref "JP11") (pin "1") (pinfunction "1_1") (pintype "passive"))
      (node (ref "TPA_L-") (pin "TP") (pinfunction "TP_TP") (pintype "input"))
    )
    (net (code "11") (name "BQ_CE") (class "Default")
      (node (ref "JP1") (pin "5") (pinfunction "5_5") (pintype "passive"))
    )
    (net (code "12") (name "BQ_CHG") (class "Default")
      (node (ref "JP1") (pin "7") (pinfunction "7_7") (pintype "passive"))
    )
    (net (code "13") (name "BQ_ISET") (class "Default")
      (node (ref "JP1") (pin "4") (pinfunction "4_4") (pintype "passive"))
    )
    (net (code "14") (name "BQ_LOAD_OUT") (class "Default")
      (node (ref "JP1") (pin "8") (pinfunction "8_8") (pintype "passive"))
      (node (ref "JP4") (pin "6") (pinfunction "6_6") (pintype "passive"))
    )
    (net (code "15") (name "BQ_PGOOD") (class "Default")
      (node (ref "JP1") (pin "6") (pinfunction "6_6") (pintype "passive"))
    )
    (net (code "16") (name "BQ_THERM") (class "Default")
      (node (ref "JP1") (pin "3") (pinfunction "3_3") (pintype "passive"))
    )
    (net (code "17") (name "BQ_USB_VBUS") (class "Default")
      (node (ref "BQ_USB_VBUS") (pin "TP") (pinfunction "TP_TP") (pintype "input"))
      (node (ref "D12") (pin "1") (pinfunction "K_1") (pintype "bidirectional"))
      (node (ref "JP1") (pin "1") (pinfunction "1_1") (pintype "passive"))
    )
    (net (code "18") (name "GND") (class "Default")
      (node (ref "5VG") (pin "TP") (pinfunction "TP_TP") (pintype "input"))
      (node (ref "C1") (pin "2") (pinfunction "2_2") (pintype "passive"))
      (node (ref "C11") (pin "2") (pinfunction "2_2") (pintype "passive"))
      (node (ref "C12") (pin "1") (pinfunction "1_1") (pintype "passive"))
      (node (ref "C13") (pin "1") (pinfunction "1_1") (pintype "passive"))
      (node (ref "C14") (pin "1") (pinfunction "1_1") (pintype "passive"))
      (node (ref "C15") (pin "1") (pinfunction "1_1") (pintype "passive"))
      (node (ref "C16") (pin "1") (pinfunction "1_1") (pintype "passive"))
      (node (ref "C17") (pin "1") (pinfunction "1_1") (pintype "passive"))
      (node (ref "C18") (pin "1") (pinfunction "1_1") (pintype "passive"))
      (node (ref "C19") (pin "1") (pinfunction "1_1") (pintype "passive"))
      (node (ref "C2") (pin "2") (pinfunction "2_2") (pintype "passive"))
      (node (ref "C20") (pin "1") (pinfunction "1_1") (pintype "passive"))
      (node (ref "C21") (pin "1") (pinfunction "1_1") (pintype "passive"))
      (node (ref "C22") (pin "1") (pinfunction "1_1") (pintype "passive"))
      (node (ref "C23") (pin "1") (pinfunction "1_1") (pintype "passive"))
      (node (ref "C24") (pin "1") (pinfunction "1_1") (pintype "passive"))
      (node (ref "C25") (pin "1") (pinfunction "1_1") (pintype "passive"))
      (node (ref "C26") (pin "1") (pinfunction "1_1") (pintype "passive"))
      (node (ref "C27") (pin "1") (pinfunction "1_1") (pintype "passive"))
      (node (ref "C28") (pin "1") (pinfunction "1_1") (pintype "passive"))
      (node (ref "C29") (pin "1") (pinfunction "1_1") (pintype "passive"))
      (node (ref "C3") (pin "2") (pinfunction "2_2") (pintype "passive"))
      (node (ref "C5") (pin "2") (pinfunction "2_2") (pintype "passive"))
      (node (ref "D1") (pin "GND") (pinfunction "GND_GND") (pintype "bidirectional"))
      (node (ref "D10") (pin "GND") (pinfunction "GND_GND") (pintype "bidirectional"))
      (node (ref "D11") (pin "GND") (pinfunction "GND_GND") (pintype "bidirectional"))
      (node (ref "D13") (pin "GND") (pinfunction "GND_GND") (pintype "bidirectional"))
      (node (ref "D2") (pin "GND") (pinfunction "GND_GND") (pintype "bidirectional"))
      (node (ref "D3") (pin "GND") (pinfunction "GND_GND") (pintype "bidirectional"))
      (node (ref "D4") (pin "GND") (pinfunction "GND_GND") (pintype "bidirectional"))
      (node (ref "D5") (pin "GND") (pinfunction "GND_GND") (pintype "bidirectional"))
      (node (ref "D6") (pin "GND") (pinfunction "GND_GND") (pintype "bidirectional"))
      (node (ref "D7") (pin "GND") (pinfunction "GND_GND") (pintype "bidirectional"))
      (node (ref "D8") (pin "GND") (pinfunction "GND_GND") (pintype "bidirectional"))
      (node (ref "D9") (pin "GND") (pinfunction "GND_GND") (pintype "bidirectional"))
      (node (ref "FB2") (pin "2") (pinfunction "2_2") (pintype "bidirectional"))
      (node (ref "IC1") (pin "2") (pinfunction "GND_1_2") (pintype "bidirectional"))
      (node (ref "IC1") (pin "5") (pinfunction "GND_2_5") (pintype "bidirectional"))
      (node (ref "IC2") (pin "1") (pinfunction "CTG_1") (pintype "bidirectional"))
      (node (ref "IC2") (pin "4") (pinfunction "GND_4") (pintype "bidirectional"))
      (node (ref "IC2") (pin "6") (pinfunction "QSTRT_6") (pintype "bidirectional"))
      (node (ref "IC2") (pin "9") (pinfunction "EP_9") (pintype "bidirectional"))
      (node (ref "IC3") (pin "13") (pinfunction "EP_13") (pintype "bidirectional"))
      (node (ref "IC3") (pin "5") (pinfunction "GND_5") (pintype "bidirectional"))
      (node (ref "J3") (pin "1") (pinfunction "1_1") (pintype "bidirectional"))
      (node (ref "J3") (pin "6") (pinfunction "6_6") (pintype "bidirectional"))
      (node (ref "J4") (pin "2") (pinfunction "2_2") (pintype "bidirectional"))
      (node (ref "J4") (pin "4") (pinfunction "4_4") (pintype "bidirectional"))
      (node (ref "J4") (pin "6") (pinfunction "6_6") (pintype "bidirectional"))
      (node (ref "JP1") (pin "11") (pinfunction "11_11") (pintype "passive"))
      (node (ref "JP1") (pin "2") (pinfunction "2_2") (pintype "passive"))
      (node (ref "JP1") (pin "9") (pinfunction "9_9") (pintype "passive"))
      (node (ref "JP4") (pin "2") (pinfunction "2_2") (pintype "passive"))
      (node (ref "JP4") (pin "5") (pinfunction "5_5") (pintype "passive"))
      (node (ref "JP5") (pin "1") (pinfunction "1_1") (pintype "passive"))
      (node (ref "JP6") (pin "1") (pinfunction "1_1") (pintype "passive"))
      (node (ref "LED2") (pin "C") (pinfunction "C_C") (pintype "passive"))
      (node (ref "Q1") (pin "1") (pinfunction "S_1_1") (pintype "bidirectional"))
      (node (ref "Q1") (pin "2") (pinfunction "S_2_2") (pintype "bidirectional"))
      (node (ref "Q1") (pin "3") (pinfunction "S_3_3") (pintype "bidirectional"))
      (node (ref "Q2") (pin "1") (pinfunction "S_1_1") (pintype "bidirectional"))
      (node (ref "Q2") (pin "2") (pinfunction "S_2_2") (pintype "bidirectional"))
      (node (ref "Q2") (pin "3") (pinfunction "S_3_3") (pintype "bidirectional"))
      (node (ref "R27") (pin "2") (pinfunction "2_2") (pintype "passive"))
      (node (ref "R4") (pin "1") (pinfunction "1_1") (pintype "passive"))
      (node (ref "R5") (pin "2") (pinfunction "2_2") (pintype "passive"))
      (node (ref "S1") (pin "1") (pinfunction "1_1") (pintype "bidirectional"))
      (node (ref "SCLG") (pin "TP") (pinfunction "TP_TP") (pintype "input"))
      (node (ref "SDAG") (pin "TP") (pinfunction "TP_TP") (pintype "input"))
      (node (ref "U$1") (pin "G") (pinfunction "G_G") (pintype "bidirectional"))
      (node (ref "U$1") (pin "GND") (pinfunction "GND_GND") (pintype "bidirectional"))
      (node (ref "U$1") (pin "GND_MIC") (pinfunction "MIC_GND_GND_MIC") (pintype "bidirectional"))
      (node (ref "U$1") (pin "INGND1") (pinfunction "INGND1_INGND1") (pintype "bidirectional"))
      (node (ref "U$1") (pin "INGND2") (pinfunction "INGND2_INGND2") (pintype "bidirectional"))
      (node (ref "U$1") (pin "OUTGND") (pinfunction "OUTGND_OUTGND") (pintype "bidirectional"))
      (node (ref "U$7") (pin "2") (pinfunction "2_2") (pintype "passive"))
      (node (ref "U8") (pin "10") (pinfunction "PIN10_10") (pintype "power_in"))
      (node (ref "U8") (pin "15") (pinfunction "PIN15_15") (pintype "power_in"))
      (node (ref "U8") (pin "16") (pinfunction "PIN16_16") (pintype "power_in"))
      (node (ref "U8") (pin "17") (pinfunction "COM3_17") (pintype "bidirectional"))
      (node (ref "U8") (pin "18") (pinfunction "COM2_18") (pintype "bidirectional"))
      (node (ref "U8") (pin "2") (pinfunction "GND_2") (pintype "power_in"))
      (node (ref "U8") (pin "25") (pinfunction "GNDIO_25") (pintype "power_in"))
      (node (ref "U8") (pin "5") (pinfunction "PS1_5") (pintype "input"))
      (node (ref "U8") (pin "6") (pinfunction "PS0_6") (pintype "input"))
      (node (ref "VBAT1") (pin "TP") (pinfunction "TP_TP") (pintype "input"))
      (node (ref "VR1") (pin "3") (pinfunction "CW_3") (pintype "bidirectional"))
    )
    (net (code "19") (name "HYD_COM1") (class "Default")
      (node (ref "HYD_COM1") (pin "TP") (pinfunction "TP_TP") (pintype "input"))
      (node (ref "J2") (pin "3") (pinfunction "3_3") (pintype "bidirectional"))
      (node (ref "K1") (pin "3") (pinfunction "COM_1_3") (pintype "bidirectional"))
    )
    (net (code "20") (name "HYD_COM2") (class "Default")
      (node (ref "HYD_COM2") (pin "TP") (pinfunction "TP_TP") (pintype "input"))
      (node (ref "J2") (pin "4") (pinfunction "4_4") (pintype "bidirectional"))
      (node (ref "K2") (pin "3") (pinfunction "COM_1_3") (pintype "bidirectional"))
    )
    (net (code "21") (name "HYD_RX_IN1") (class "Default")
      (node (ref "C8") (pin "1") (pinfunction "P$1_1") (pintype "passive"))
      (node (ref "K1") (pin "2") (pinfunction "NC_1_2") (pintype "bidirectional"))
      (node (ref "R6") (pin "1") (pinfunction "1_1") (pintype "passive"))
    )
    (net (code "22") (name "HYD_RX_INPUT") (class "Default")
      (node (ref "C9") (pin "1") (pinfunction "P$1_1") (pintype "passive"))
      (node (ref "HYD_RX_AMP") (pin "TP") (pinfunction "TP_TP") (pintype "input"))
      (node (ref "R12") (pin "1") (pinfunction "1_1") (pintype "passive"))
      (node (ref "R12") (pin "2") (pinfunction "2_2") (pintype "passive"))
      (node (ref "U$1") (pin "MIC") (pinfunction "MIC_MIC") (pintype "input"))
      (node (ref "U1") (pin "4") (pinfunction "OUT_4") (pintype "bidirectional"))
    )
    (net (code "23") (name "HYD_TX_OUT1") (class "Default")
      (node (ref "IC3") (pin "6") (pinfunction "VO2_6") (pintype "bidirectional"))
      (node (ref "K1") (pin "4") (pinfunction "NO_1_4") (pintype "bidirectional"))
    )
    (net (code "24") (name "HYD_TX_OUT2") (class "Default")
      (node (ref "IC3") (pin "7") (pinfunction "VO1_7") (pintype "bidirectional"))
      (node (ref "K2") (pin "4") (pinfunction "NO_1_4") (pintype "bidirectional"))
    )
    (net (code "25") (name "HYD_TX_SIG") (class "Default")
      (node (ref "HYD_TX_SIG") (pin "TP") (pinfunction "TP_TP") (pintype "input"))
      (node (ref "IC3") (pin "3") (pinfunction "DIN_3") (pintype "bidirectional"))
      (node (ref "U$1") (pin "3") (pinfunction "3_3") (pintype "bidirectional"))
    )
    (net (code "26") (name "IMU_CLK1") (class "Default")
      (node (ref "C16") (pin "2") (pinfunction "2_2") (pintype "passive"))
      (node (ref "U8") (pin "27") (pinfunction "XIN32_27") (pintype "input"))
      (node (ref "Y1") (pin "1") (pinfunction "1_1") (pintype "bidirectional"))
    )
    (net (code "27") (name "IMU_CLK2") (class "Default")
      (node (ref "C17") (pin "2") (pinfunction "2_2") (pintype "passive"))
      (node (ref "U8") (pin "26") (pinfunction "XOUT32_26") (pintype "output"))
      (node (ref "Y1") (pin "2") (pinfunction "2_2") (pintype "bidirectional"))
    )
    (net (code "28") (name "LED_BRIDGE") (class "Default")
      (node (ref "D6") (pin "DI") (pinfunction "DI_DI") (pintype "bidirectional"))
      (node (ref "D8") (pin "DO") (pinfunction "DO_DO") (pintype "bidirectional"))
    )
    (net (code "29") (name "LED_DIN") (class "Default")
      (node (ref "R13") (pin "1") (pinfunction "1_1") (pintype "passive"))
      (node (ref "U$1") (pin "2") (pinfunction "2_2") (pintype "bidirectional"))
    )
    (net (code "30") (name "LED_DOUT") (class "Default")
      (node (ref "D11") (pin "DO") (pinfunction "DO_DO") (pintype "bidirectional"))
      (node (ref "J3") (pin "5") (pinfunction "5_5") (pintype "bidirectional"))
    )
    (net (code "31") (name "NC_BCLK") (class "Default")
      (node (ref "U$1") (pin "21") (pinfunction "21_21") (pintype "bidirectional"))
    )
    (net (code "32") (name "NC_DIN") (class "Default")
      (node (ref "U$1") (pin "7") (pinfunction "7_7") (pintype "bidirectional"))
    )
    (net (code "33") (name "NC_DOUT") (class "Default")
      (node (ref "U$1") (pin "8") (pinfunction "8_8") (pintype "bidirectional"))
    )
    (net (code "34") (name "NC_LRCLK") (class "Default")
      (node (ref "U$1") (pin "20") (pinfunction "20_20") (pintype "bidirectional"))
    )
    (net (code "35") (name "NC_MCLK") (class "Default")
      (node (ref "U$1") (pin "23") (pinfunction "23_23") (pintype "bidirectional"))
    )
    (net (code "36") (name "NC_MEMCS") (class "Default")
      (node (ref "U$1") (pin "6") (pinfunction "6_6") (pintype "bidirectional"))
    )
    (net (code "37") (name "NC_MISO") (class "Default")
      (node (ref "U$1") (pin "12") (pinfunction "12_12") (pintype "bidirectional"))
    )
    (net (code "38") (name "NC_MOSI") (class "Default")
      (node (ref "U$1") (pin "11") (pinfunction "11_11") (pintype "bidirectional"))
    )
    (net (code "39") (name "NC_SCK") (class "Default")
      (node (ref "U$1") (pin "13") (pinfunction "13_13") (pintype "bidirectional"))
    )
    (net (code "40") (name "NC_SDCS") (class "Default")
      (node (ref "U$1") (pin "10") (pinfunction "10_10") (pintype "bidirectional"))
    )
    (net (code "41") (name "NC_VOL") (class "Default")
      (node (ref "U$1") (pin "15") (pinfunction "15_15") (pintype "bidirectional"))
    )
    (net (code "42") (name "Net-(C7-P$1)") (class "Default")
      (node (ref "C7") (pin "1") (pinfunction "P$1_1") (pintype "passive"))
      (node (ref "R6") (pin "2") (pinfunction "2_2") (pintype "passive"))
      (node (ref "R7") (pin "1") (pinfunction "1_1") (pintype "passive"))
    )
    (net (code "43") (name "Net-(C8-P$2)") (class "Default")
      (node (ref "C8") (pin "2") (pinfunction "P$2_2") (pintype "passive"))
      (node (ref "R10") (pin "1") (pinfunction "1_1") (pintype "passive"))
      (node (ref "R9") (pin "2") (pinfunction "2_2") (pintype "passive"))
      (node (ref "U1") (pin "1") (pinfunction "IN+_1") (pintype "bidirectional"))
    )
    (net (code "44") (name "Net-(C9-P$2)") (class "Default")
      (node (ref "C9") (pin "2") (pinfunction "P$2_2") (pintype "passive"))
      (node (ref "R11") (pin "1") (pinfunction "1_1") (pintype "passive"))
      (node (ref "R8") (pin "2") (pinfunction "2_2") (pintype "passive"))
      (node (ref "U1") (pin "3") (pinfunction "IN-_3") (pintype "bidirectional"))
    )
    (net (code "45") (name "Net-(C10-P$1)") (class "Default")
      (node (ref "C10") (pin "1") (pinfunction "P$1_1") (pintype "passive"))
      (node (ref "R8") (pin "1") (pinfunction "1_1") (pintype "passive"))
    )
    (net (code "46") (name "Net-(D1-PadDI)") (class "Default")
      (node (ref "D1") (pin "DI") (pinfunction "DI_DI") (pintype "bidirectional"))
      (node (ref "D13") (pin "DO") (pinfunction "DO_DO") (pintype "bidirectional"))
    )
    (net (code "47") (name "Net-(D1-PadDO)") (class "Default")
      (node (ref "D1") (pin "DO") (pinfunction "DO_DO") (pintype "bidirectional"))
      (node (ref "D2") (pin "DI") (pinfunction "DI_DI") (pintype "bidirectional"))
    )
    (net (code "48") (name "Net-(D2-PadDO)") (class "Default")
      (node (ref "D2") (pin "DO") (pinfunction "DO_DO") (pintype "bidirectional"))
      (node (ref "D3") (pin "DI") (pinfunction "DI_DI") (pintype "bidirectional"))
    )
    (net (code "49") (name "Net-(D3-PadDO)") (class "Default")
      (node (ref "D3") (pin "DO") (pinfunction "DO_DO") (pintype "bidirectional"))
      (node (ref "D4") (pin "DI") (pinfunction "DI_DI") (pintype "bidirectional"))
    )
    (net (code "50") (name "Net-(D4-PadDO)") (class "Default")
      (node (ref "D4") (pin "DO") (pinfunction "DO_DO") (pintype "bidirectional"))
      (node (ref "D5") (pin "DI") (pinfunction "DI_DI") (pintype "bidirectional"))
    )
    (net (code "51") (name "Net-(D5-PadDO)") (class "Default")
      (node (ref "D5") (pin "DO") (pinfunction "DO_DO") (pintype "bidirectional"))
      (node (ref "D8") (pin "DI") (pinfunction "DI_DI") (pintype "bidirectional"))
    )
    (net (code "52") (name "Net-(D6-PadDO)") (class "Default")
      (node (ref "D6") (pin "DO") (pinfunction "DO_DO") (pintype "bidirectional"))
      (node (ref "D7") (pin "DI") (pinfunction "DI_DI") (pintype "bidirectional"))
    )
    (net (code "53") (name "Net-(D7-PadDO)") (class "Default")
      (node (ref "D7") (pin "DO") (pinfunction "DO_DO") (pintype "bidirectional"))
      (node (ref "D9") (pin "DI") (pinfunction "DI_DI") (pintype "bidirectional"))
    )
    (net (code "54") (name "Net-(D10-PadDI)") (class "Default")
      (node (ref "D10") (pin "DI") (pinfunction "DI_DI") (pintype "bidirectional"))
      (node (ref "D9") (pin "DO") (pinfunction "DO_DO") (pintype "bidirectional"))
    )
    (net (code "55") (name "Net-(D10-PadDO)") (class "Default")
      (node (ref "D10") (pin "DO") (pinfunction "DO_DO") (pintype "bidirectional"))
      (node (ref "D11") (pin "DI") (pinfunction "DI_DI") (pintype "bidirectional"))
    )
    (net (code "56") (name "Net-(D12-A)") (class "Default")
      (node (ref "D12") (pin "2") (pinfunction "A_2") (pintype "bidirectional"))
      (node (ref "J4") (pin "3") (pinfunction "3_3") (pintype "bidirectional"))
    )
    (net (code "57") (name "Net-(D13-PadDI)") (class "Default")
      (node (ref "D13") (pin "DI") (pinfunction "DI_DI") (pintype "bidirectional"))
      (node (ref "R13") (pin "2") (pinfunction "2_2") (pintype "passive"))
    )
    (net (code "58") (name "Net-(FB3-Pad2)") (class "Default")
      (node (ref "FB3") (pin "2") (pinfunction "2_2") (pintype "bidirectional"))
      (node (ref "JP14") (pin "2") (pinfunction "2_2") (pintype "passive"))
    )
    (net (code "59") (name "Net-(IC1-ENABLE)") (class "Default")
      (node (ref "IC1") (pin "3") (pinfunction "ENABLE_3") (pintype "bidirectional"))
      (node (ref "R1") (pin "1") (pinfunction "1_1") (pintype "passive"))
    )
    (net (code "60") (name "Net-(IC2-VDD)") (class "Default")
      (node (ref "IC2") (pin "3") (pinfunction "VDD_3") (pintype "bidirectional"))
      (node (ref "JP8") (pin "2") (pinfunction "2_2") (pintype "passive"))
    )
    (net (code "61") (name "Net-(IC3-EN1)") (class "Default")
      (node (ref "IC3") (pin "1") (pinfunction "EN1_1") (pintype "bidirectional"))
      (node (ref "IC4") (pin "2") (pinfunction "COM_2_2") (pintype "bidirectional"))
      (node (ref "R4") (pin "2") (pinfunction "2_2") (pintype "passive"))
    )
    (net (code "62") (name "Net-(IC3-EN2)") (class "Default")
      (node (ref "IC3") (pin "2") (pinfunction "EN2_2") (pintype "bidirectional"))
      (node (ref "IC4") (pin "1") (pinfunction "COM_1_1") (pintype "bidirectional"))
      (node (ref "R5") (pin "1") (pinfunction "1_1") (pintype "passive"))
    )
    (net (code "63") (name "Net-(IC3-VOUT)") (class "Default")
      (node (ref "C2") (pin "1") (pinfunction "1_1") (pintype "passive"))
      (node (ref "IC3") (pin "10") (pinfunction "VOUT_10") (pintype "bidirectional"))
    )
    (net (code "64") (name "Net-(JP5-Pad2)") (class "Default")
      (node (ref "JP5") (pin "2") (pinfunction "2_2") (pintype "passive"))
      (node (ref "U$7") (pin "4") (pinfunction "4_4") (pintype "passive"))
    )
    (net (code "65") (name "Net-(JP6-Pad2)") (class "Default")
      (node (ref "JP6") (pin "2") (pinfunction "2_2") (pintype "passive"))
      (node (ref "U$7") (pin "7") (pinfunction "7_7") (pintype "passive"))
    )
    (net (code "66") (name "Net-(JP12-Pad1)") (class "Default")
      (node (ref "JP12") (pin "1") (pinfunction "1_1") (pintype "passive"))
      (node (ref "TPA_R+") (pin "TP") (pinfunction "TP_TP") (pintype "input"))
    )
    (net (code "67") (name "Net-(JP13-Pad1)") (class "Default")
      (node (ref "JP13") (pin "1") (pinfunction "1_1") (pintype "passive"))
      (node (ref "TPA_R-") (pin "TP") (pinfunction "TP_TP") (pintype "input"))
    )
    (net (code "68") (name "Net-(LED2-PadA)") (class "Default")
      (node (ref "LED2") (pin "A") (pinfunction "A_A") (pintype "passive"))
      (node (ref "R29") (pin "1") (pinfunction "1_1") (pintype "passive"))
    )
    (net (code "69") (name "Net-(Q1-G)") (class "Default")
      (node (ref "Q1") (pin "4") (pinfunction "G_4") (pintype "bidirectional"))
      (node (ref "R23") (pin "2") (pinfunction "2_2") (pintype "passive"))
    )
    (net (code "70") (name "Net-(Q2-G)") (class "Default")
      (node (ref "Q2") (pin "4") (pinfunction "G_4") (pintype "bidirectional"))
      (node (ref "R14") (pin "2") (pinfunction "2_2") (pintype "passive"))
    )
    (net (code "71") (name "Net-(R11-Pad2)") (class "Default")
      (node (ref "R11") (pin "2") (pinfunction "2_2") (pintype "passive"))
      (node (ref "R12") (pin "3") (pinfunction "3_3") (pintype "passive"))
    )
    (net (code "72") (name "Net-(U8-CAP)") (class "Default")
      (node (ref "C21") (pin "2") (pinfunction "2_2") (pintype "passive"))
      (node (ref "U8") (pin "9") (pinfunction "CAP_9") (pintype "passive"))
    )
    (net (code "73") (name "Net-(U8-NBOOT_LOAD_PIN)") (class "Default")
      (node (ref "R32") (pin "1") (pinfunction "1_1") (pintype "passive"))
      (node (ref "U8") (pin "4") (pinfunction "NBOOT_LOAD_PIN_4") (pintype "bidirectional"))
    )
    (net (code "74") (name "PAM_CN1") (class "Default")
      (node (ref "C4") (pin "2") (pinfunction "2_2") (pintype "passive"))
      (node (ref "IC3") (pin "4") (pinfunction "CN1_4") (pintype "bidirectional"))
    )
    (net (code "75") (name "PAM_CN2") (class "Default")
      (node (ref "C6") (pin "2") (pinfunction "2_2") (pintype "passive"))
      (node (ref "IC3") (pin "8") (pinfunction "CN2_8") (pintype "bidirectional"))
    )
    (net (code "76") (name "PAM_CP1") (class "Default")
      (node (ref "C4") (pin "1") (pinfunction "1_1") (pintype "passive"))
      (node (ref "IC3") (pin "9") (pinfunction "CP1_9") (pintype "bidirectional"))
    )
    (net (code "77") (name "PAM_CP2") (class "Default")
      (node (ref "C6") (pin "1") (pinfunction "1_1") (pintype "passive"))
      (node (ref "IC3") (pin "11") (pinfunction "CP2_11") (pintype "bidirectional"))
    )
    (net (code "78") (name "PB1K_EN") (class "Default")
      (node (ref "J4") (pin "5") (pinfunction "5_5") (pintype "bidirectional"))
      (node (ref "JP4") (pin "4") (pinfunction "4_4") (pintype "passive"))
      (node (ref "S1") (pin "2") (pinfunction "2_2") (pintype "bidirectional"))
    )
    (net (code "79") (name "PB1K_LB") (class "Default")
      (node (ref "JP4") (pin "3") (pinfunction "3_3") (pintype "passive"))
    )
    (net (code "80") (name "SCL_3V") (class "Default")
      (node (ref "IC2") (pin "7") (pinfunction "SCL_7") (pintype "bidirectional"))
      (node (ref "JP3") (pin "2") (pinfunction "2_2") (pintype "passive"))
      (node (ref "Q4") (pin "2") (pinfunction "S_2") (pintype "bidirectional"))
      (node (ref "R3") (pin "1") (pinfunction "1_1") (pintype "passive"))
      (node (ref "SCL_3V") (pin "TP") (pinfunction "TP_TP") (pintype "input"))
      (node (ref "U$7") (pin "8") (pinfunction "8_8") (pintype "passive"))
      (node (ref "U8") (pin "19") (pinfunction "COM1_19") (pintype "bidirectional"))
    )
    (net (code "81") (name "SCL_5V") (class "Default")
      (node (ref "IC1") (pin "6") (pinfunction "BUS1_6") (pintype "bidirectional"))
      (node (ref "J3") (pin "4") (pinfunction "4_4") (pintype "bidirectional"))
      (node (ref "Q4") (pin "3") (pinfunction "D_3") (pintype "bidirectional"))
      (node (ref "R18") (pin "1") (pinfunction "1_1") (pintype "passive"))
      (node (ref "SCL_5V") (pin "TP") (pinfunction "TP_TP") (pintype "input"))
    )
    (net (code "82") (name "SDA_3V") (class "Default")
      (node (ref "IC2") (pin "8") (pinfunction "SDA_8") (pintype "bidirectional"))
      (node (ref "JP2") (pin "2") (pinfunction "2_2") (pintype "passive"))
      (node (ref "Q3") (pin "2") (pinfunction "S_2") (pintype "bidirectional"))
      (node (ref "R2") (pin "1") (pinfunction "1_1") (pintype "passive"))
      (node (ref "SDA_3V") (pin "TP") (pinfunction "TP_TP") (pintype "input"))
      (node (ref "U$7") (pin "9") (pinfunction "9_9") (pintype "passive"))
      (node (ref "U8") (pin "20") (pinfunction "COM0_20") (pintype "bidirectional"))
    )
    (net (code "83") (name "SDA_5V") (class "Default")
      (node (ref "IC1") (pin "4") (pinfunction "BUS2_4") (pintype "bidirectional"))
      (node (ref "J3") (pin "3") (pinfunction "3_3") (pintype "bidirectional"))
      (node (ref "Q3") (pin "3") (pinfunction "D_3") (pintype "bidirectional"))
      (node (ref "R17") (pin "1") (pinfunction "1_1") (pintype "passive"))
      (node (ref "SDA_5V") (pin "TP") (pinfunction "TP_TP") (pintype "input"))
    )
    (net (code "84") (name "TPA_L+") (class "Default")
      (node (ref "U$1") (pin "OUTL") (pinfunction "OUTL_OUTL") (pintype "output"))
      (node (ref "U$7") (pin "6") (pinfunction "6_6") (pintype "passive"))
    )
    (net (code "85") (name "TPA_R+") (class "Default")
      (node (ref "U$1") (pin "OUTR") (pinfunction "OUTR_OUTR") (pintype "output"))
      (node (ref "U$7") (pin "5") (pinfunction "5_5") (pintype "passive"))
    )
    (net (code "86") (name "TPA_SHDN") (class "Default")
      (node (ref "U$7") (pin "3") (pinfunction "3_3") (pintype "passive"))
    )
    (net (code "87") (name "TXRX_OUT1") (class "Default")
      (node (ref "K1") (pin "8") (pinfunction "-_8") (pintype "bidirectional"))
      (node (ref "Q1") (pin "5") (pinfunction "D_1_5") (pintype "bidirectional"))
      (node (ref "Q1") (pin "6") (pinfunction "D_2_6") (pintype "bidirectional"))
      (node (ref "Q1") (pin "7") (pinfunction "D_3_7") (pintype "bidirectional"))
      (node (ref "Q1") (pin "8") (pinfunction "D_4_8") (pintype "bidirectional"))
    )
    (net (code "88") (name "TXRX_OUT2") (class "Default")
      (node (ref "K2") (pin "8") (pinfunction "-_8") (pintype "bidirectional"))
      (node (ref "Q2") (pin "5") (pinfunction "D_1_5") (pintype "bidirectional"))
      (node (ref "Q2") (pin "6") (pinfunction "D_2_6") (pintype "bidirectional"))
      (node (ref "Q2") (pin "7") (pinfunction "D_3_7") (pintype "bidirectional"))
      (node (ref "Q2") (pin "8") (pinfunction "D_4_8") (pintype "bidirectional"))
    )
    (net (code "89") (name "TXRX_RELAY") (class "Default")
      (node (ref "R14") (pin "1") (pinfunction "1_1") (pintype "passive"))
      (node (ref "R23") (pin "1") (pinfunction "1_1") (pintype "passive"))
      (node (ref "R27") (pin "1") (pinfunction "1_1") (pintype "passive"))
      (node (ref "R29") (pin "2") (pinfunction "2_2") (pintype "passive"))
      (node (ref "TP_TXRX") (pin "TP") (pinfunction "TP_TP") (pintype "input"))
      (node (ref "U$1") (pin "4") (pinfunction "4_4") (pintype "bidirectional"))
    )
    (net (code "90") (name "VBAT") (class "Default")
      (node (ref "C1") (pin "1") (pinfunction "1_1") (pintype "passive"))
      (node (ref "C11") (pin "1") (pinfunction "1_1") (pintype "passive"))
      (node (ref "IC2") (pin "2") (pinfunction "CELL_2") (pintype "bidirectional"))
      (node (ref "J4") (pin "1") (pinfunction "1_1") (pintype "bidirectional"))
      (node (ref "JP1") (pin "10") (pinfunction "10_10") (pintype "passive"))
      (node (ref "JP8") (pin "3") (pinfunction "3_3") (pintype "passive"))
      (node (ref "VBAT") (pin "TP") (pinfunction "TP_TP") (pintype "input"))
    )
    (net (code "91") (name "VOL_POT_SIG") (class "Default")
      (node (ref "J2") (pin "1") (pinfunction "1_1") (pintype "bidirectional"))
      (node (ref "U$1") (pin "14") (pinfunction "14_14") (pintype "bidirectional"))
      (node (ref "VR1") (pin "2") (pinfunction "WIPER_2") (pintype "bidirectional"))
    )
    (net (code "92") (name "unconnected-(IC2-~{ALRT}-Pad5)") (class "Default")
      (node (ref "IC2") (pin "5") (pinfunction "~{ALRT}_5") (pintype "bidirectional"))
    )
    (net (code "93") (name "unconnected-(K1-COM_2-Pad6)") (class "Default")
      (node (ref "K1") (pin "6") (pinfunction "COM_2_6") (pintype "bidirectional"))
    )
    (net (code "94") (name "unconnected-(K1-NC_2-Pad7)") (class "Default")
      (node (ref "K1") (pin "7") (pinfunction "NC_2_7") (pintype "bidirectional"))
    )
    (net (code "95") (name "unconnected-(K1-NO_2-Pad5)") (class "Default")
      (node (ref "K1") (pin "5") (pinfunction "NO_2_5") (pintype "bidirectional"))
    )
    (net (code "96") (name "unconnected-(K2-COM_2-Pad6)") (class "Default")
      (node (ref "K2") (pin "6") (pinfunction "COM_2_6") (pintype "bidirectional"))
    )
    (net (code "97") (name "unconnected-(K2-NC_2-Pad7)") (class "Default")
      (node (ref "K2") (pin "7") (pinfunction "NC_2_7") (pintype "bidirectional"))
    )
    (net (code "98") (name "unconnected-(K2-NO_2-Pad5)") (class "Default")
      (node (ref "K2") (pin "5") (pinfunction "NO_2_5") (pintype "bidirectional"))
    )
    (net (code "99") (name "unconnected-(U$1-Pad0)") (class "Default")
      (node (ref "U$1") (pin "0") (pinfunction "0_0") (pintype "bidirectional"))
    )
    (net (code "100") (name "unconnected-(U$1-Pad1)") (class "Default")
      (node (ref "U$1") (pin "1") (pinfunction "1_1") (pintype "bidirectional"))
    )
    (net (code "101") (name "unconnected-(U$1-Pad5)") (class "Default")
      (node (ref "U$1") (pin "5") (pinfunction "5_5") (pintype "bidirectional"))
    )
    (net (code "102") (name "unconnected-(U$1-Pad9)") (class "Default")
      (node (ref "U$1") (pin "9") (pinfunction "9_9") (pintype "bidirectional"))
    )
    (net (code "103") (name "unconnected-(U$1-Pad22)") (class "Default")
      (node (ref "U$1") (pin "22") (pinfunction "22_22") (pintype "bidirectional"))
    )
    (net (code "104") (name "unconnected-(U$1-PadINL)") (class "Default")
      (node (ref "U$1") (pin "INL") (pinfunction "INL_INL") (pintype "input"))
    )
    (net (code "105") (name "unconnected-(U$1-PadINR)") (class "Default")
      (node (ref "U$1") (pin "INR") (pinfunction "INR_INR") (pintype "input"))
    )
    (net (code "106") (name "unconnected-(U$1-PadVOL)") (class "Default")
      (node (ref "U$1") (pin "VOL") (pinfunction "VOL_VOL") (pintype "input"))
    )
    (net (code "107") (name "unconnected-(U$1-PadVOL_3.3V)") (class "Default")
      (node (ref "U$1") (pin "VOL_3.3V") (pinfunction "VOL_3.3V_VOL_3.3V") (pintype "bidirectional"))
    )
    (net (code "108") (name "unconnected-(U$1-PadVOL_GND)") (class "Default")
      (node (ref "U$1") (pin "VOL_GND") (pinfunction "VOL_GND_VOL_GND") (pintype "bidirectional"))
    )
    (net (code "109") (name "unconnected-(U8-INT-Pad14)") (class "Default")
      (node (ref "U8") (pin "14") (pinfunction "INT_14") (pintype "output"))
    )
    (net (code "110") (name "unconnected-(U8-NRESET-Pad11)") (class "Default")
      (node (ref "U8") (pin "11") (pinfunction "NRESET_11") (pintype "input"))
    )
  )
)
